# line_follower.net
KiCad netlist of a schematic drawn in EAGLE
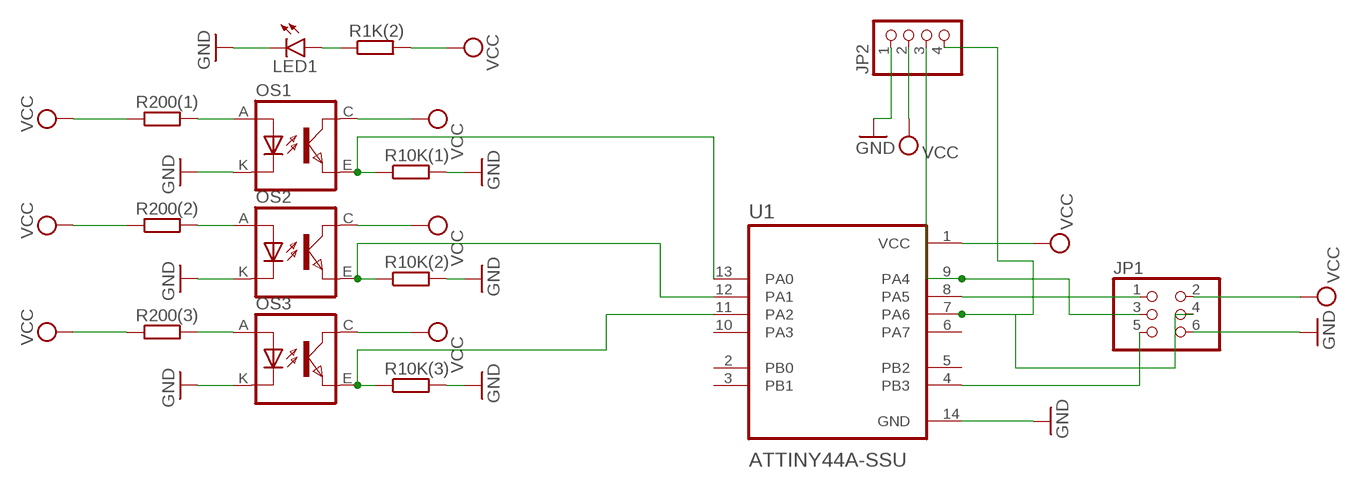
[diagram p0: schematic, sheet 1]

(export (version "E")
  (design (tool "Eeschema 10.0.6"))
  (components
    (comp (ref "JP1")
      (value "PINHD-2X03_2.54-SMD")
      (footprint "eagle-import:2X03SMD")
      (libsource (lib "eagle-import") (part "PINHD-2X03_2.54-SMD"))
    )
    (comp (ref "JP2")
      (value "PINHD-1X04_2.54-SMD")
      (footprint "eagle-import:1X04SMD")
      (libsource (lib "eagle-import") (part "PINHD-1X04_2.54-SMD"))
    )
    (comp (ref "LED1")
      (value "LEDCHIPLED_1206")
      (footprint "eagle-import:CHIPLED_1206")
      (libsource (lib "eagle-import") (part "LEDCHIPLED_1206"))
    )
    (comp (ref "OS1")
      (value "TCRT5000")
      (footprint "eagle-import:TCRT5000")
      (libsource (lib "eagle-import") (part "TCRT5000"))
    )
    (comp (ref "OS2")
      (value "TCRT5000")
      (footprint "eagle-import:TCRT5000")
      (libsource (lib "eagle-import") (part "TCRT5000"))
    )
    (comp (ref "OS3")
      (value "TCRT5000")
      (footprint "eagle-import:TCRT5000")
      (libsource (lib "eagle-import") (part "TCRT5000"))
    )
    (comp (ref "R1K(2)")
      (value "R-EU_R1206")
      (footprint "eagle-import:R1206")
      (libsource (lib "eagle-import") (part "R-EU_R1206"))
    )
    (comp (ref "R10K(1)")
      (value "R-EU_R1206")
      (footprint "eagle-import:R1206")
      (libsource (lib "eagle-import") (part "R-EU_R1206"))
    )
    (comp (ref "R10K(2)")
      (value "R-EU_R1206")
      (footprint "eagle-import:R1206")
      (libsource (lib "eagle-import") (part "R-EU_R1206"))
    )
    (comp (ref "R10K(3)")
      (value "R-EU_R1206")
      (footprint "eagle-import:R1206")
      (libsource (lib "eagle-import") (part "R-EU_R1206"))
    )
    (comp (ref "R200(1)")
      (value "R-EU_R1206")
      (footprint "eagle-import:R1206")
      (libsource (lib "eagle-import") (part "R-EU_R1206"))
    )
    (comp (ref "R200(2)")
      (value "R-EU_R1206")
      (footprint "eagle-import:R1206")
      (libsource (lib "eagle-import") (part "R-EU_R1206"))
    )
    (comp (ref "R200(3)")
      (value "R-EU_R1206")
      (footprint "eagle-import:R1206")
      (libsource (lib "eagle-import") (part "R-EU_R1206"))
    )
    (comp (ref "U1")
      (value "ATTINY44A-SSU")
      (footprint "eagle-import:SOIC127P600X175-14N")
      (fields (field (name "MF") "Microchip"))
      (libsource (lib "eagle-import") (part "ATTINY44A-SSU"))
    )
  )
  (nets
    (net (code "1") (name "GND") (class "Default")
      (node (ref "JP1") (pin "6") (pinfunction "6_6") (pintype "passive"))
      (node (ref "JP2") (pin "1") (pinfunction "1_1") (pintype "passive"))
      (node (ref "LED1") (pin "C") (pinfunction "C_C") (pintype "passive"))
      (node (ref "OS1") (pin "K") (pinfunction "CATHODE_K") (pintype "passive"))
      (node (ref "OS2") (pin "K") (pinfunction "CATHODE_K") (pintype "passive"))
      (node (ref "OS3") (pin "K") (pinfunction "CATHODE_K") (pintype "passive"))
      (node (ref "R10K(1)") (pin "2") (pinfunction "2_2") (pintype "passive"))
      (node (ref "R10K(2)") (pin "2") (pinfunction "2_2") (pintype "passive"))
      (node (ref "R10K(3)") (pin "2") (pinfunction "2_2") (pintype "passive"))
      (node (ref "U1") (pin "14") (pinfunction "GND_14") (pintype "power_in"))
    )
    (net (code "2") (name "Net-(LED1-PadA)") (class "Default")
      (node (ref "LED1") (pin "A") (pinfunction "A_A") (pintype "passive"))
      (node (ref "R1K(2)") (pin "1") (pinfunction "1_1") (pintype "passive"))
    )
    (net (code "3") (name "Net-(OS1-ANODE)") (class "Default")
      (node (ref "OS1") (pin "A") (pinfunction "ANODE_A") (pintype "passive"))
      (node (ref "R200(1)") (pin "2") (pinfunction "2_2") (pintype "passive"))
    )
    (net (code "4") (name "Net-(OS1-EMITTER)") (class "Default")
      (node (ref "OS1") (pin "E") (pinfunction "EMITTER_E") (pintype "passive"))
      (node (ref "R10K(1)") (pin "1") (pinfunction "1_1") (pintype "passive"))
      (node (ref "U1") (pin "13") (pinfunction "PA0_13") (pintype "bidirectional"))
    )
    (net (code "5") (name "Net-(OS2-ANODE)") (class "Default")
      (node (ref "OS2") (pin "A") (pinfunction "ANODE_A") (pintype "passive"))
      (node (ref "R200(2)") (pin "2") (pinfunction "2_2") (pintype "passive"))
    )
    (net (code "6") (name "Net-(OS2-EMITTER)") (class "Default")
      (node (ref "OS2") (pin "E") (pinfunction "EMITTER_E") (pintype "passive"))
      (node (ref "R10K(2)") (pin "1") (pinfunction "1_1") (pintype "passive"))
      (node (ref "U1") (pin "12") (pinfunction "PA1_12") (pintype "bidirectional"))
    )
    (net (code "7") (name "Net-(OS3-ANODE)") (class "Default")
      (node (ref "OS3") (pin "A") (pinfunction "ANODE_A") (pintype "passive"))
      (node (ref "R200(3)") (pin "2") (pinfunction "2_2") (pintype "passive"))
    )
    (net (code "8") (name "Net-(OS3-EMITTER)") (class "Default")
      (node (ref "OS3") (pin "E") (pinfunction "EMITTER_E") (pintype "passive"))
      (node (ref "R10K(3)") (pin "1") (pinfunction "1_1") (pintype "passive"))
      (node (ref "U1") (pin "11") (pinfunction "PA2_11") (pintype "bidirectional"))
    )
    (net (code "9") (name "Net-(U1-PA4)") (class "Default")
      (node (ref "JP1") (pin "3") (pinfunction "3_3") (pintype "passive"))
      (node (ref "JP2") (pin "3") (pinfunction "3_3") (pintype "passive"))
      (node (ref "U1") (pin "9") (pinfunction "PA4_9") (pintype "bidirectional"))
    )
    (net (code "10") (name "Net-(U1-PA5)") (class "Default")
      (node (ref "JP1") (pin "1") (pinfunction "1_1") (pintype "passive"))
      (node (ref "U1") (pin "8") (pinfunction "PA5_8") (pintype "bidirectional"))
    )
    (net (code "11") (name "Net-(U1-PA6)") (class "Default")
      (node (ref "JP1") (pin "4") (pinfunction "4_4") (pintype "passive"))
      (node (ref "JP2") (pin "4") (pinfunction "4_4") (pintype "passive"))
      (node (ref "U1") (pin "7") (pinfunction "PA6_7") (pintype "bidirectional"))
    )
    (net (code "12") (name "Net-(U1-PB3)") (class "Default")
      (node (ref "JP1") (pin "5") (pinfunction "5_5") (pintype "passive"))
      (node (ref "U1") (pin "4") (pinfunction "PB3_4") (pintype "bidirectional"))
    )
    (net (code "13") (name "VCC") (class "Default")
      (node (ref "JP1") (pin "2") (pinfunction "2_2") (pintype "passive"))
      (node (ref "JP2") (pin "2") (pinfunction "2_2") (pintype "passive"))
      (node (ref "OS1") (pin "C") (pinfunction "COLLECTOR_C") (pintype "passive"))
      (node (ref "OS2") (pin "C") (pinfunction "COLLECTOR_C") (pintype "passive"))
      (node (ref "OS3") (pin "C") (pinfunction "COLLECTOR_C") (pintype "passive"))
      (node (ref "R1K(2)") (pin "2") (pinfunction "2_2") (pintype "passive"))
      (node (ref "R200(1)") (pin "1") (pinfunction "1_1") (pintype "passive"))
      (node (ref "R200(2)") (pin "1") (pinfunction "1_1") (pintype "passive"))
      (node (ref "R200(3)") (pin "1") (pinfunction "1_1") (pintype "passive"))
      (node (ref "U1") (pin "1") (pinfunction "VCC_1") (pintype "power_in"))
    )
    (net (code "14") (name "unconnected-(U1-PA3-Pad10)") (class "Default")
      (node (ref "U1") (pin "10") (pinfunction "PA3_10") (pintype "bidirectional"))
    )
    (net (code "15") (name "unconnected-(U1-PA7-Pad6)") (class "Default")
      (node (ref "U1") (pin "6") (pinfunction "PA7_6") (pintype "bidirectional"))
    )
    (net (code "16") (name "unconnected-(U1-PB0-Pad2)") (class "Default")
      (node (ref "U1") (pin "2") (pinfunction "PB0_2") (pintype "bidirectional"))
    )
    (net (code "17") (name "unconnected-(U1-PB1-Pad3)") (class "Default")
      (node (ref "U1") (pin "3") (pinfunction "PB1_3") (pintype "bidirectional"))
    )
    (net (code "18") (name "unconnected-(U1-PB2-Pad5)") (class "Default")
      (node (ref "U1") (pin "5") (pinfunction "PB2_5") (pintype "bidirectional"))
    )
  )
)
